# Pot.net
KiCad netlist of a schematic drawn in EAGLE
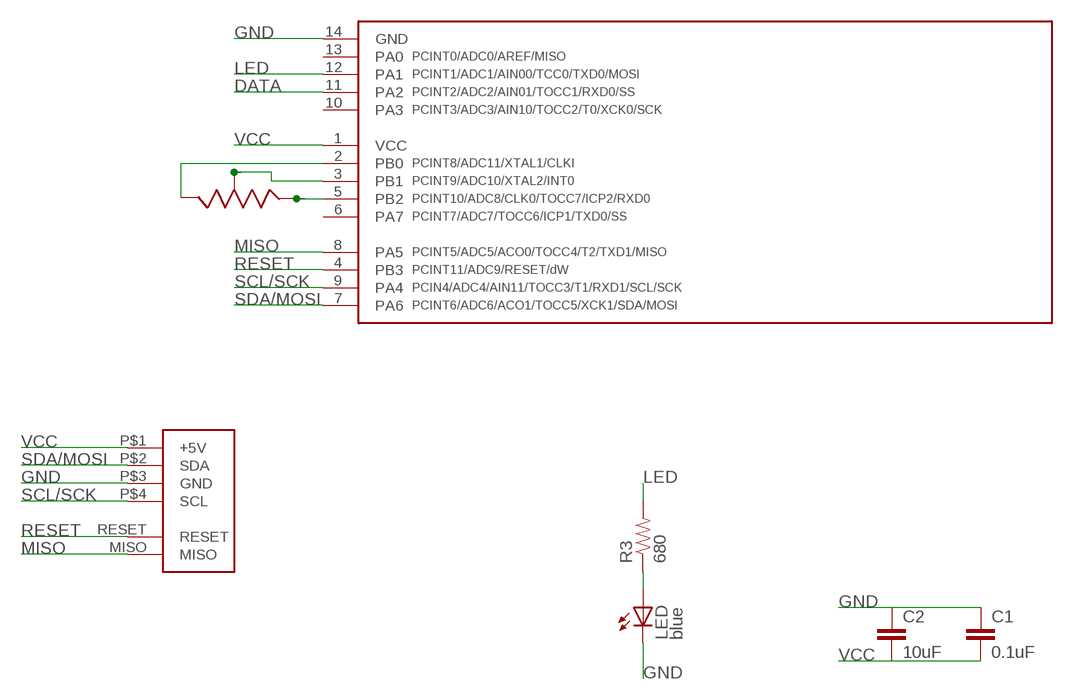
[diagram p0: schematic, sheet 1]

(export (version "E")
  (design (tool "Eeschema 10.0.6"))
  (components
    (comp (ref "C1")
      (value "0.1uF")
      (footprint "eagle-import:0805")
      (libsource (lib "eagle-import") (part "CAP0805"))
    )
    (comp (ref "C2")
      (value "10uF")
      (footprint "eagle-import:0805")
      (libsource (lib "eagle-import") (part "CAP0805"))
    )
    (comp (ref "LED")
      (value "blue")
      (footprint "eagle-import:CHIPLED_1206")
      (libsource (lib "eagle-import") (part "LEDCHIPLED_1206"))
    )
    (comp (ref "R3")
      (value "680")
      (footprint "eagle-import:0805")
      (libsource (lib "eagle-import") (part "RESISTOR0805-RES"))
    )
    (comp (ref "U$2")
      (value "BOURNS_PRS11S")
      (footprint "eagle-import:PRS11S")
      (libsource (lib "eagle-import") (part "BOURNS_PRS11S"))
    )
    (comp (ref "U$3")
      (value "TINY841")
      (footprint "eagle-import:SOIC14")
      (libsource (lib "eagle-import") (part "TINY841"))
    )
    (comp (ref "U$4")
      (value "FOOTPRINT")
      (footprint "eagle-import:FOOTPRINT")
      (libsource (lib "eagle-import") (part "FOOTPRINT"))
    )
  )
  (nets
    (net (code "1") (name "/DATA") (class "Default")
      (node (ref "U$3") (pin "11") (pinfunction "PA2_11") (pintype "bidirectional"))
    )
    (net (code "2") (name "/GND") (class "Default")
      (node (ref "C1") (pin "1") (pinfunction "1_1") (pintype "passive"))
      (node (ref "C2") (pin "1") (pinfunction "1_1") (pintype "passive"))
      (node (ref "LED") (pin "C") (pinfunction "C_C") (pintype "passive"))
      (node (ref "U$3") (pin "14") (pinfunction "GND_14") (pintype "bidirectional"))
      (node (ref "U$4") (pin "P$3") (pinfunction "GND_P$3") (pintype "power_in"))
    )
    (net (code "3") (name "/LED") (class "Default")
      (node (ref "R3") (pin "2") (pinfunction "2_2") (pintype "passive"))
      (node (ref "U$3") (pin "12") (pinfunction "PA1_12") (pintype "bidirectional"))
    )
    (net (code "4") (name "/MISO") (class "Default")
      (node (ref "U$3") (pin "8") (pinfunction "PA5_8") (pintype "bidirectional"))
      (node (ref "U$4") (pin "MISO") (pinfunction "MISO_MISO") (pintype "bidirectional"))
    )
    (net (code "5") (name "/RESET") (class "Default")
      (node (ref "U$3") (pin "4") (pinfunction "PB3_4") (pintype "bidirectional"))
      (node (ref "U$4") (pin "RESET") (pinfunction "RESET_RESET") (pintype "bidirectional"))
    )
    (net (code "6") (name "/SCL{slash}SCK") (class "Default")
      (node (ref "U$3") (pin "9") (pinfunction "PA4_9") (pintype "bidirectional"))
      (node (ref "U$4") (pin "P$4") (pinfunction "SCL_P$4") (pintype "bidirectional"))
    )
    (net (code "7") (name "/SDA{slash}MOSI") (class "Default")
      (node (ref "U$3") (pin "7") (pinfunction "PA6_7") (pintype "bidirectional"))
      (node (ref "U$4") (pin "P$2") (pinfunction "SDA_P$2") (pintype "bidirectional"))
    )
    (net (code "8") (name "/VCC") (class "Default")
      (node (ref "C1") (pin "2") (pinfunction "2_2") (pintype "passive"))
      (node (ref "C2") (pin "2") (pinfunction "2_2") (pintype "passive"))
      (node (ref "U$3") (pin "1") (pinfunction "VCC_1") (pintype "bidirectional"))
      (node (ref "U$4") (pin "P$1") (pinfunction "+5V_P$1") (pintype "power_in"))
    )
    (net (code "9") (name "Net-(LED-PadA)") (class "Default")
      (node (ref "LED") (pin "A") (pinfunction "A_A") (pintype "passive"))
      (node (ref "R3") (pin "1") (pinfunction "1_1") (pintype "passive"))
    )
    (net (code "10") (name "Net-(U$2-P1)") (class "Default")
      (node (ref "U$2") (pin "2") (pinfunction "P1_2") (pintype "bidirectional"))
      (node (ref "U$3") (pin "5") (pinfunction "PB2_5") (pintype "bidirectional"))
    )
    (net (code "11") (name "Net-(U$2-P2)") (class "Default")
      (node (ref "U$2") (pin "3") (pinfunction "P2_3") (pintype "bidirectional"))
      (node (ref "U$3") (pin "3") (pinfunction "PB1_3") (pintype "bidirectional"))
    )
    (net (code "12") (name "Net-(U$2-P3)") (class "Default")
      (node (ref "U$2") (pin "1") (pinfunction "P3_1") (pintype "bidirectional"))
      (node (ref "U$3") (pin "2") (pinfunction "PB0_2") (pintype "bidirectional"))
    )
    (net (code "13") (name "unconnected-(U$3-PA0-Pad13)") (class "Default")
      (node (ref "U$3") (pin "13") (pinfunction "PA0_13") (pintype "bidirectional"))
    )
    (net (code "14") (name "unconnected-(U$3-PA3-Pad10)") (class "Default")
      (node (ref "U$3") (pin "10") (pinfunction "PA3_10") (pintype "bidirectional"))
    )
    (net (code "15") (name "unconnected-(U$3-PA7-Pad6)") (class "Default")
      (node (ref "U$3") (pin "6") (pinfunction "PA7_6") (pintype "bidirectional"))
    )
  )
)
